# Arduino_DUE_V02b_1.net
KiCad netlist of a schematic drawn in Altium Designer
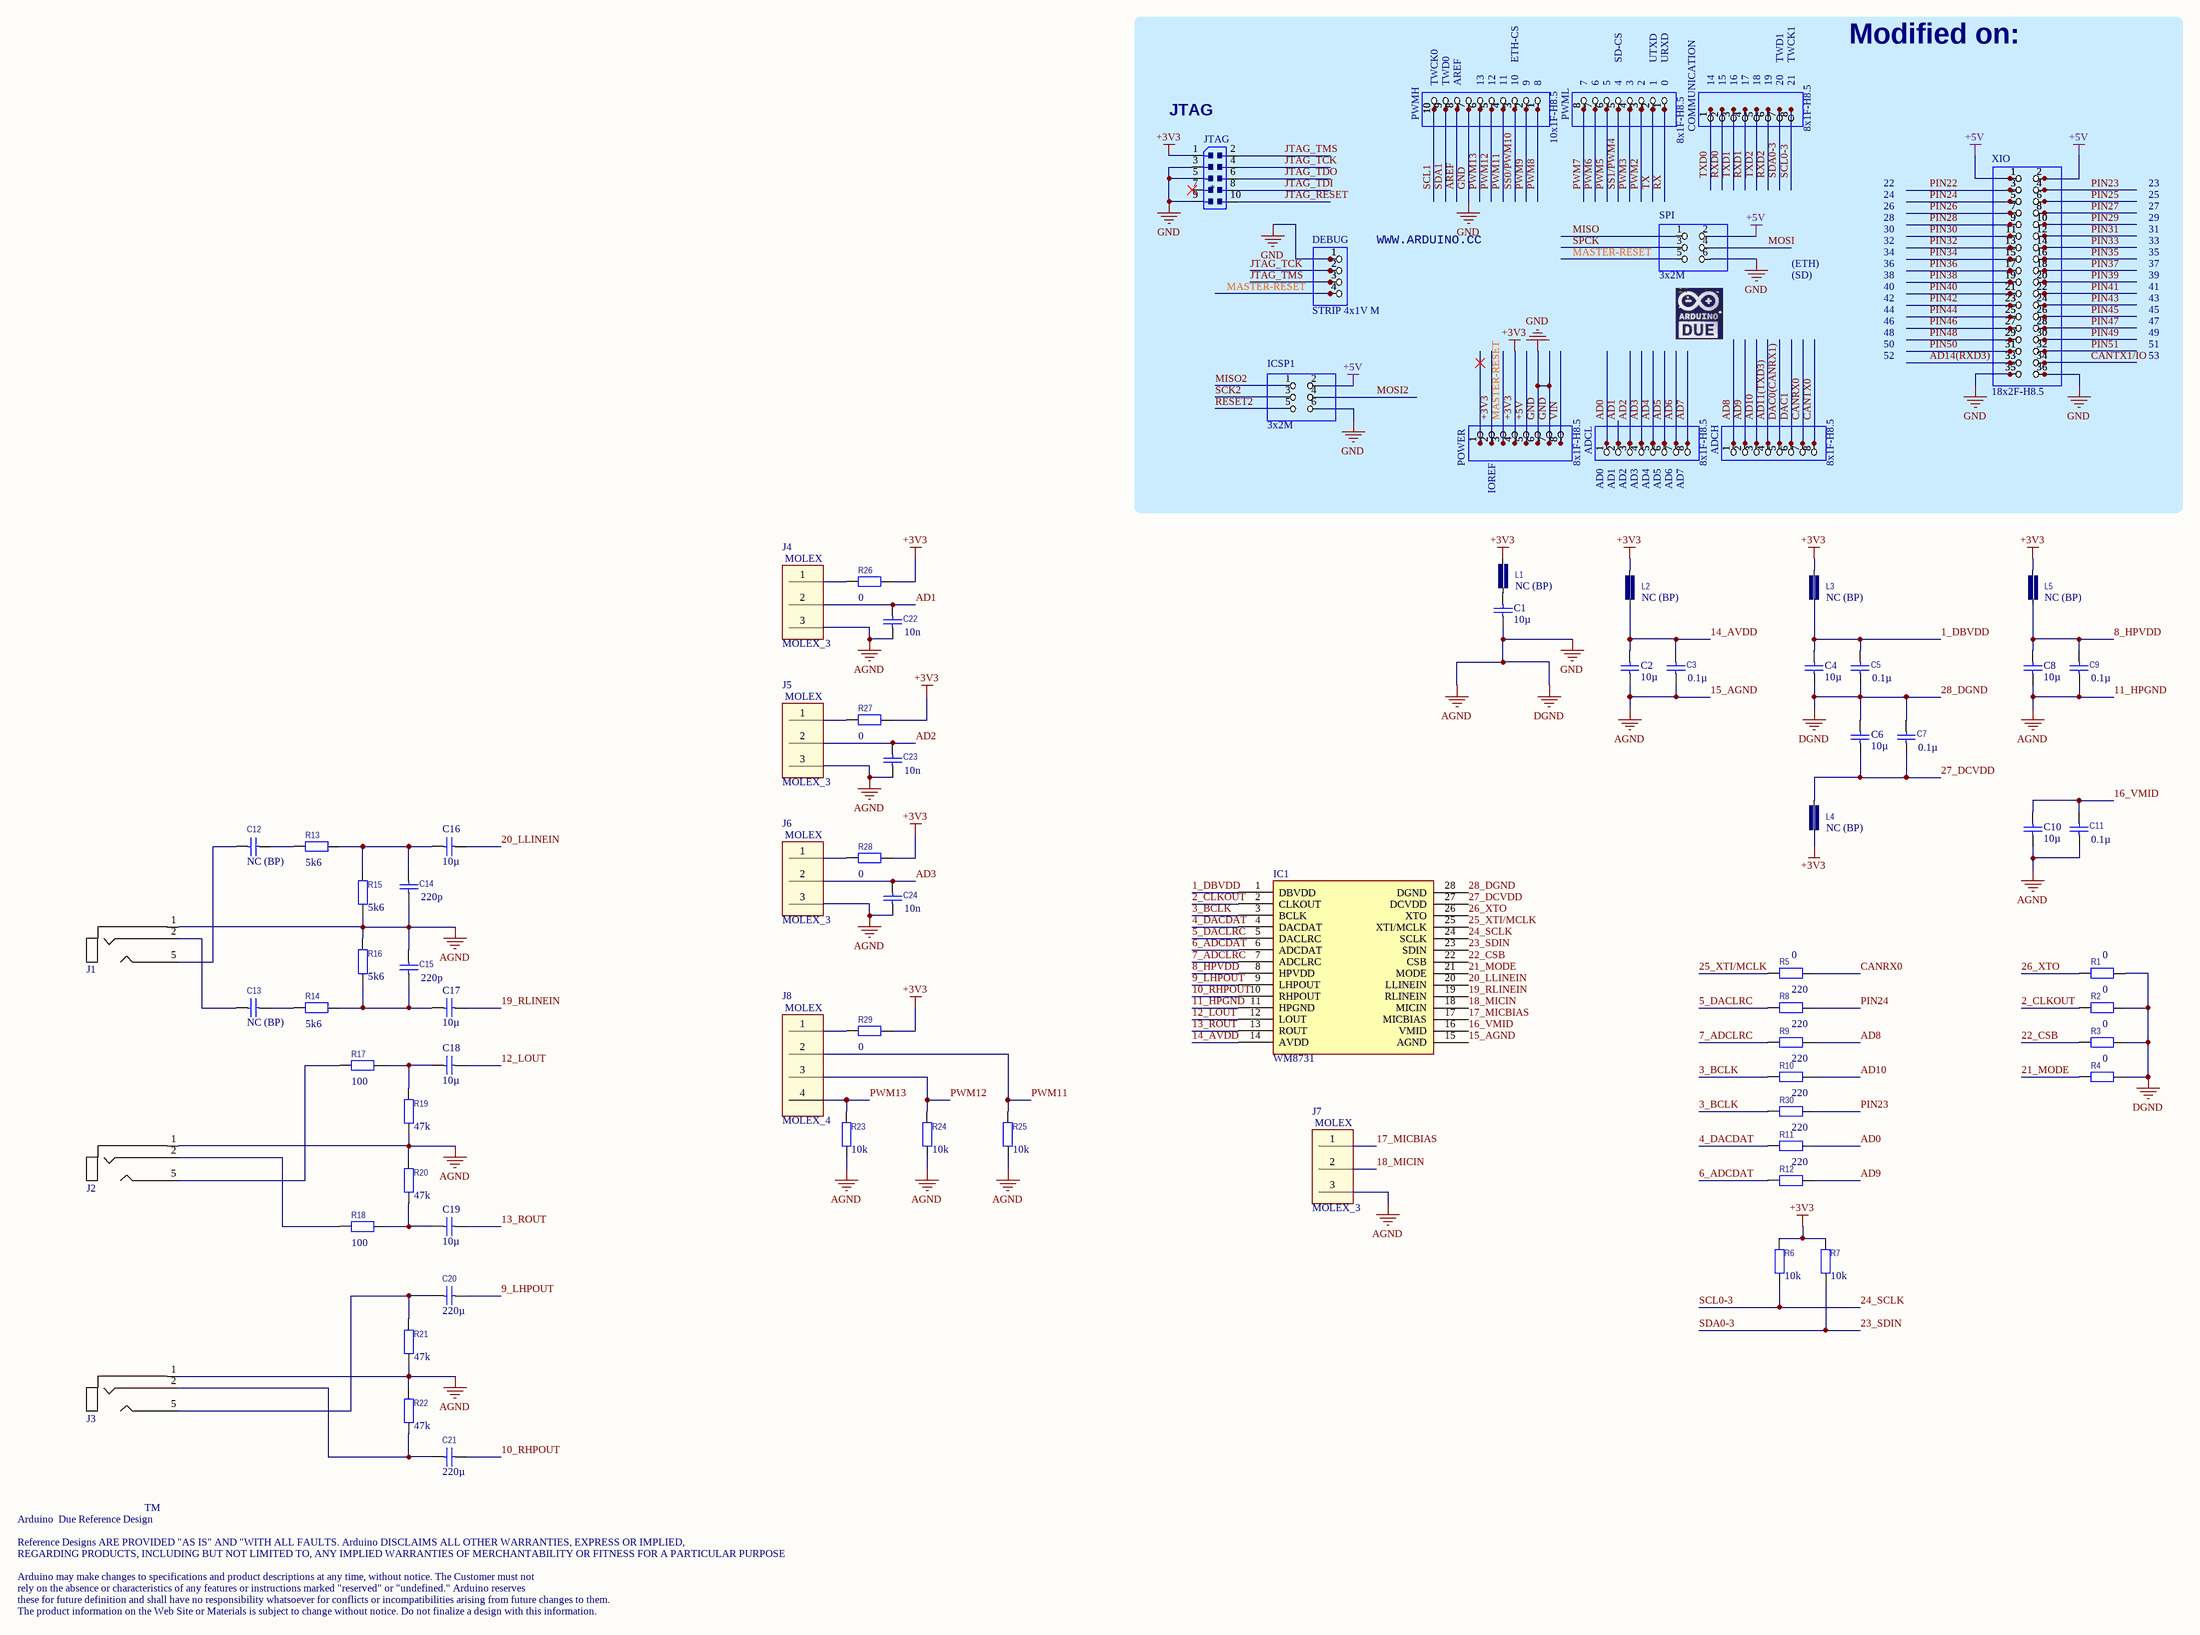
[diagram p0: Arduino_DUE_V02b_1.SchDoc]

(export (version "E")
  (design (tool "Eeschema 10.0.6"))
  (components
    (comp (ref "ADCH") (value "8x1F-H8.5") (footprint "1X08") (libsource (lib "SmartPrj") (part "PINHD-1X8")))
    (comp (ref "ADCL") (value "8x1F-H8.5") (footprint "1X08") (libsource (lib "SmartPrj") (part "PINHD-1X8")))
    (comp (ref "C1")
      (value "10µ")
      (footprint "0603_s")
      (fields (field (name "Comment") "Cap"))
      (libsource (lib "Cap") (part "Cap"))
    )
    (comp (ref "C2")
      (value "10µ")
      (footprint "0603_s")
      (fields (field (name "Comment") "Cap"))
      (libsource (lib "Cap") (part "Cap"))
    )
    (comp (ref "C3")
      (value "0.1µ")
      (footprint "0402_s")
      (fields (field (name "PARTNUMBER") "EA00008430") (field (name "Comment") "Capacitor"))
      (libsource (lib "AVLDiTEST Bauteile") (part "Capacitor"))
    )
    (comp (ref "C4")
      (value "10µ")
      (footprint "0603_s")
      (fields (field (name "Comment") "Cap"))
      (libsource (lib "Cap") (part "Cap"))
    )
    (comp (ref "C5")
      (value "0.1µ")
      (footprint "0402_s")
      (fields (field (name "PARTNUMBER") "EA00008430") (field (name "Comment") "Capacitor"))
      (libsource (lib "AVLDiTEST Bauteile") (part "Capacitor"))
    )
    (comp (ref "C6")
      (value "10µ")
      (footprint "0603_s")
      (fields (field (name "Comment") "Cap"))
      (libsource (lib "Cap") (part "Cap"))
    )
    (comp (ref "C7")
      (value "0.1µ")
      (footprint "0402_s")
      (fields (field (name "PARTNUMBER") "EA00008430") (field (name "Comment") "Capacitor"))
      (libsource (lib "AVLDiTEST Bauteile") (part "Capacitor"))
    )
    (comp (ref "C8")
      (value "10µ")
      (footprint "0603_s")
      (fields (field (name "Comment") "Cap"))
      (libsource (lib "Cap") (part "Cap"))
    )
    (comp (ref "C9")
      (value "0.1µ")
      (footprint "0402_s")
      (fields (field (name "PARTNUMBER") "EA00008430") (field (name "Comment") "Capacitor"))
      (libsource (lib "AVLDiTEST Bauteile") (part "Capacitor"))
    )
    (comp (ref "C10")
      (value "10µ")
      (footprint "0603_s")
      (fields (field (name "Comment") "Cap"))
      (libsource (lib "Cap") (part "Cap"))
    )
    (comp (ref "C11")
      (value "0.1µ")
      (footprint "0402_s")
      (fields (field (name "PARTNUMBER") "EA00008430") (field (name "Comment") "Capacitor"))
      (libsource (lib "AVLDiTEST Bauteile") (part "Capacitor"))
    )
    (comp (ref "C12")
      (value "NC (BP)")
      (footprint "0402_s")
      (fields (field (name "PARTNUMBER") "EA00008430") (field (name "Comment") "Capacitor"))
      (libsource (lib "AVLDiTEST Bauteile") (part "Capacitor"))
    )
    (comp (ref "C13")
      (value "NC (BP)")
      (footprint "0402_s")
      (fields (field (name "PARTNUMBER") "EA00008430") (field (name "Comment") "Capacitor"))
      (libsource (lib "AVLDiTEST Bauteile") (part "Capacitor"))
    )
    (comp (ref "C14")
      (value "220p")
      (footprint "0402_s")
      (fields (field (name "PARTNUMBER") "EA00008430") (field (name "Comment") "Capacitor"))
      (libsource (lib "AVLDiTEST Bauteile") (part "Capacitor"))
    )
    (comp (ref "C15")
      (value "220p")
      (footprint "0402_s")
      (fields (field (name "PARTNUMBER") "EA00008430") (field (name "Comment") "Capacitor"))
      (libsource (lib "AVLDiTEST Bauteile") (part "Capacitor"))
    )
    (comp (ref "C16")
      (value "10µ")
      (footprint "0603_s")
      (fields (field (name "Comment") "Cap"))
      (libsource (lib "Cap") (part "Cap"))
    )
    (comp (ref "C17")
      (value "10µ")
      (footprint "0603_s")
      (fields (field (name "Comment") "Cap"))
      (libsource (lib "Cap") (part "Cap"))
    )
    (comp (ref "C18")
      (value "10µ")
      (footprint "0603_s")
      (fields (field (name "Comment") "Cap"))
      (libsource (lib "Cap") (part "Cap"))
    )
    (comp (ref "C19")
      (value "10µ")
      (footprint "0603_s")
      (fields (field (name "Comment") "Cap"))
      (libsource (lib "Cap") (part "Cap"))
    )
    (comp (ref "C20")
      (value "220µ")
      (footprint "EEEFK0J221P")
      (fields (field (name "PARTNUMBER") "EA00008430") (field (name "Comment") "Capacitor"))
      (libsource (lib "AVLDiTEST Bauteile") (part "Capacitor"))
    )
    (comp (ref "C21")
      (value "220µ")
      (footprint "EEEFK0J221P")
      (fields (field (name "PARTNUMBER") "EA00008430") (field (name "Comment") "Capacitor"))
      (libsource (lib "AVLDiTEST Bauteile") (part "Capacitor"))
    )
    (comp (ref "C22")
      (value "10n")
      (footprint "0402_s")
      (fields (field (name "PARTNUMBER") "EA00008430") (field (name "Comment") "Capacitor"))
      (libsource (lib "AVLDiTEST Bauteile") (part "Capacitor"))
    )
    (comp (ref "C23")
      (value "10n")
      (footprint "0402_s")
      (fields (field (name "PARTNUMBER") "EA00008430") (field (name "Comment") "Capacitor"))
      (libsource (lib "AVLDiTEST Bauteile") (part "Capacitor"))
    )
    (comp (ref "C24")
      (value "10n")
      (footprint "0402_s")
      (fields (field (name "PARTNUMBER") "EA00008430") (field (name "Comment") "Capacitor"))
      (libsource (lib "AVLDiTEST Bauteile") (part "Capacitor"))
    )
    (comp (ref "COMMUNICATION")
      (value "8x1F-H8.5")
      (footprint "1X08")
      (libsource (lib "SmartPrj") (part "PINHD-1X8"))
    )
    (comp (ref "DEBUG")
      (value "STRIP 4x1V M")
      (footprint "1X04")
      (libsource (lib "pinhead") (part "PINHD-1X4"))
    )
    (comp (ref "IC1") (value "WM8731") (footprint "SSOP28") (libsource (lib "CODEC_SHIELD") (part "WM8731")))
    (comp (ref "ICSP1") (value "3x2M") (footprint "2X03") (libsource (lib "SmartPrj") (part "PINHD-2X3")))
    (comp (ref "J1")
      (value "FC68131")
      (footprint "FC68131")
      (libsource (lib "CODEC_SHIELD") (part "FC68131"))
    )
    (comp (ref "J2")
      (value "FC68131")
      (footprint "FC68131")
      (libsource (lib "CODEC_SHIELD") (part "FC68131"))
    )
    (comp (ref "J3")
      (value "FC68131")
      (footprint "FC68131")
      (libsource (lib "CODEC_SHIELD") (part "FC68131"))
    )
    (comp (ref "J4") (value "MOLEX_3") (footprint "254_3") (libsource (lib "CODEC_SHIELD") (part "MOLEX_3")))
    (comp (ref "J5") (value "MOLEX_3") (footprint "254_3") (libsource (lib "CODEC_SHIELD") (part "MOLEX_3")))
    (comp (ref "J6") (value "MOLEX_3") (footprint "254_3") (libsource (lib "CODEC_SHIELD") (part "MOLEX_3")))
    (comp (ref "J7") (value "MOLEX_3") (footprint "254_3") (libsource (lib "CODEC_SHIELD") (part "MOLEX_3")))
    (comp (ref "J8") (value "MOLEX_4") (footprint "254_4") (libsource (lib "CODEC_SHIELD") (part "MOLEX_4")))
    (comp (ref "JTAG")
      (value "*")
      (footprint "PINHEAD_2X05_127")
      (libsource (lib "Arduino_Wifi_shield_v018_tG") (part "PINHEAD_PINHD-2X5PASSO127"))
    )
    (comp (ref "L1")
      (value "NC (BP)")
      (footprint "0402_S")
      (fields (field (name "PARTNUMBER") "EA00008563"))
      (libsource (lib "AVLDiTEST Bauteile") (part "Ferrite_BLM15AG121SN1"))
    )
    (comp (ref "L2")
      (value "NC (BP)")
      (footprint "0402_S")
      (fields (field (name "PARTNUMBER") "EA00008563"))
      (libsource (lib "AVLDiTEST Bauteile") (part "Ferrite_BLM15AG121SN1"))
    )
    (comp (ref "L3")
      (value "NC (BP)")
      (footprint "0402_S")
      (fields (field (name "PARTNUMBER") "EA00008563"))
      (libsource (lib "AVLDiTEST Bauteile") (part "Ferrite_BLM15AG121SN1"))
    )
    (comp (ref "L4")
      (value "NC (BP)")
      (footprint "0402_S")
      (fields (field (name "PARTNUMBER") "EA00008563"))
      (libsource (lib "AVLDiTEST Bauteile") (part "Ferrite_BLM15AG121SN1"))
    )
    (comp (ref "L5")
      (value "NC (BP)")
      (footprint "0402_S")
      (fields (field (name "PARTNUMBER") "EA00008563"))
      (libsource (lib "AVLDiTEST Bauteile") (part "Ferrite_BLM15AG121SN1"))
    )
    (comp (ref "POWER")
      (value "8x1F-H8.5")
      (footprint "1X08")
      (libsource (lib "SmartPrj") (part "PINHD-1X8"))
    )
    (comp (ref "PWMH")
      (value "10x1F-H8.5")
      (footprint "1X10")
      (libsource (lib "SmartPrj") (part "PINHD-1X10"))
    )
    (comp (ref "PWML") (value "8x1F-H8.5") (footprint "1X08") (libsource (lib "SmartPrj") (part "PINHD-1X8")))
    (comp (ref "R1")
      (value "0")
      (footprint "0402_s")
      (fields (field (name "PARTNUMBER") "EA00008473"))
      (libsource (lib "") (part "Resistor_2"))
    )
    (comp (ref "R2")
      (value "0")
      (footprint "0402_s")
      (fields (field (name "PARTNUMBER") "EA00008473"))
      (libsource (lib "") (part "Resistor_2"))
    )
    (comp (ref "R3")
      (value "0")
      (footprint "0402_s")
      (fields (field (name "PARTNUMBER") "EA00008473"))
      (libsource (lib "") (part "Resistor_2"))
    )
    (comp (ref "R4")
      (value "0")
      (footprint "0402_s")
      (fields (field (name "PARTNUMBER") "EA00008473"))
      (libsource (lib "") (part "Resistor_2"))
    )
    (comp (ref "R5")
      (value "0")
      (footprint "0402_s")
      (fields (field (name "PARTNUMBER") "EA00008473"))
      (libsource (lib "") (part "Resistor_2"))
    )
    (comp (ref "R6")
      (value "10k")
      (footprint "0402_s")
      (fields (field (name "PARTNUMBER") "EA00008473"))
      (libsource (lib "AVLDiTEST Bauteile") (part "Resistor"))
    )
    (comp (ref "R7")
      (value "10k")
      (footprint "0402_s")
      (fields (field (name "PARTNUMBER") "EA00008473"))
      (libsource (lib "AVLDiTEST Bauteile") (part "Resistor"))
    )
    (comp (ref "R8")
      (value "220")
      (footprint "0402_s")
      (fields (field (name "PARTNUMBER") "EA00008473"))
      (libsource (lib "") (part "Resistor_2"))
    )
    (comp (ref "R9")
      (value "220")
      (footprint "0402_s")
      (fields (field (name "PARTNUMBER") "EA00008473"))
      (libsource (lib "") (part "Resistor_2"))
    )
    (comp (ref "R10")
      (value "220")
      (footprint "0402_s")
      (fields (field (name "PARTNUMBER") "EA00008473"))
      (libsource (lib "") (part "Resistor_2"))
    )
    (comp (ref "R11")
      (value "220")
      (footprint "0402_s")
      (fields (field (name "PARTNUMBER") "EA00008473"))
      (libsource (lib "") (part "Resistor_2"))
    )
    (comp (ref "R12")
      (value "220")
      (footprint "0402_s")
      (fields (field (name "PARTNUMBER") "EA00008473"))
      (libsource (lib "") (part "Resistor_2"))
    )
    (comp (ref "R13")
      (value "5k6")
      (footprint "0402_s")
      (fields (field (name "PARTNUMBER") "EA00008473"))
      (libsource (lib "") (part "Resistor_1"))
    )
    (comp (ref "R14")
      (value "5k6")
      (footprint "0402_s")
      (fields (field (name "PARTNUMBER") "EA00008473"))
      (libsource (lib "") (part "Resistor_1"))
    )
    (comp (ref "R15")
      (value "5k6")
      (footprint "0402_s")
      (fields (field (name "PARTNUMBER") "EA00008473"))
      (libsource (lib "AVLDiTEST Bauteile") (part "Resistor"))
    )
    (comp (ref "R16")
      (value "5k6")
      (footprint "0402_s")
      (fields (field (name "PARTNUMBER") "EA00008473"))
      (libsource (lib "AVLDiTEST Bauteile") (part "Resistor"))
    )
    (comp (ref "R17")
      (value "100")
      (footprint "0402_s")
      (fields (field (name "PARTNUMBER") "EA00008473"))
      (libsource (lib "") (part "Resistor_1"))
    )
    (comp (ref "R18")
      (value "100")
      (footprint "0402_s")
      (fields (field (name "PARTNUMBER") "EA00008473"))
      (libsource (lib "") (part "Resistor_1"))
    )
    (comp (ref "R19")
      (value "47k")
      (footprint "0402_s")
      (fields (field (name "PARTNUMBER") "EA00008473"))
      (libsource (lib "AVLDiTEST Bauteile") (part "Resistor"))
    )
    (comp (ref "R20")
      (value "47k")
      (footprint "0402_s")
      (fields (field (name "PARTNUMBER") "EA00008473"))
      (libsource (lib "AVLDiTEST Bauteile") (part "Resistor"))
    )
    (comp (ref "R21")
      (value "47k")
      (footprint "0402_s")
      (fields (field (name "PARTNUMBER") "EA00008473"))
      (libsource (lib "AVLDiTEST Bauteile") (part "Resistor"))
    )
    (comp (ref "R22")
      (value "47k")
      (footprint "0402_s")
      (fields (field (name "PARTNUMBER") "EA00008473"))
      (libsource (lib "AVLDiTEST Bauteile") (part "Resistor"))
    )
    (comp (ref "R23")
      (value "10k")
      (footprint "0402_s")
      (fields (field (name "PARTNUMBER") "EA00008473"))
      (libsource (lib "AVLDiTEST Bauteile") (part "Resistor"))
    )
    (comp (ref "R24")
      (value "10k")
      (footprint "0402_s")
      (fields (field (name "PARTNUMBER") "EA00008473"))
      (libsource (lib "AVLDiTEST Bauteile") (part "Resistor"))
    )
    (comp (ref "R25")
      (value "10k")
      (footprint "0402_s")
      (fields (field (name "PARTNUMBER") "EA00008473"))
      (libsource (lib "AVLDiTEST Bauteile") (part "Resistor"))
    )
    (comp (ref "R26")
      (value "0")
      (footprint "0402_s")
      (fields (field (name "PARTNUMBER") "EA00008473"))
      (libsource (lib "") (part "Resistor_1"))
    )
    (comp (ref "R27")
      (value "0")
      (footprint "0402_s")
      (fields (field (name "PARTNUMBER") "EA00008473"))
      (libsource (lib "") (part "Resistor_1"))
    )
    (comp (ref "R28")
      (value "0")
      (footprint "0402_s")
      (fields (field (name "PARTNUMBER") "EA00008473"))
      (libsource (lib "") (part "Resistor_1"))
    )
    (comp (ref "R29")
      (value "0")
      (footprint "0402_s")
      (fields (field (name "PARTNUMBER") "EA00008473"))
      (libsource (lib "") (part "Resistor_1"))
    )
    (comp (ref "R30")
      (value "220")
      (footprint "0402_s")
      (fields (field (name "PARTNUMBER") "EA00008473"))
      (libsource (lib "") (part "Resistor_2"))
    )
    (comp (ref "SPI") (value "3x2M") (footprint "2X03") (libsource (lib "SmartPrj") (part "PINHD-2X3")))
    (comp (ref "XIO")
      (value "18x2F-H8.5")
      (footprint "2X18")
      (libsource (lib "SmartPrj") (part "PINHD-2X18"))
    )
  )
  (nets
    (net (code "1") (name "+3V3") (class "Default")
      (node (ref "JTAG") (pin "1") (pinfunction "1_1") (pintype "passive"))
      (node (ref "L1") (pin "2") (pinfunction "2_2") (pintype "passive"))
      (node (ref "L2") (pin "2") (pinfunction "2_2") (pintype "passive"))
      (node (ref "L3") (pin "2") (pinfunction "2_2") (pintype "passive"))
      (node (ref "L4") (pin "1") (pinfunction "1_1") (pintype "passive"))
      (node (ref "L5") (pin "2") (pinfunction "2_2") (pintype "passive"))
      (node (ref "POWER") (pin "2") (pinfunction "2_2") (pintype "passive"))
      (node (ref "POWER") (pin "4") (pinfunction "4_4") (pintype "passive"))
      (node (ref "R26") (pin "1") (pinfunction "1_1") (pintype "passive"))
      (node (ref "R27") (pin "1") (pinfunction "1_1") (pintype "passive"))
      (node (ref "R28") (pin "1") (pinfunction "1_1") (pintype "passive"))
      (node (ref "R29") (pin "1") (pinfunction "1_1") (pintype "passive"))
      (node (ref "R6") (pin "2") (pinfunction "2_2") (pintype "passive"))
      (node (ref "R7") (pin "2") (pinfunction "2_2") (pintype "passive"))
    )
    (net (code "2") (name "+5V") (class "Default")
      (node (ref "ICSP1") (pin "2") (pinfunction "2_2") (pintype "passive"))
      (node (ref "POWER") (pin "5") (pinfunction "5_5") (pintype "passive"))
      (node (ref "SPI") (pin "2") (pinfunction "2_2") (pintype "passive"))
      (node (ref "XIO") (pin "1") (pinfunction "1_1") (pintype "passive"))
      (node (ref "XIO") (pin "2") (pinfunction "2_2") (pintype "passive"))
    )
    (net (code "3") (name "/1_DBVDD") (class "Default")
      (node (ref "C4") (pin "2") (pinfunction "2_2") (pintype "passive"))
      (node (ref "C5") (pin "2") (pinfunction "2_2") (pintype "passive"))
      (node (ref "IC1") (pin "1") (pinfunction "DBVDD_1") (pintype "passive"))
      (node (ref "L3") (pin "1") (pinfunction "1_1") (pintype "passive"))
    )
    (net (code "4") (name "/2_CLKOUT") (class "Default")
      (node (ref "IC1") (pin "2") (pinfunction "CLKOUT_2") (pintype "passive"))
      (node (ref "R2") (pin "1") (pinfunction "1_1") (pintype "passive"))
    )
    (net (code "5") (name "/3_BCLK") (class "Default")
      (node (ref "IC1") (pin "3") (pinfunction "BCLK_3") (pintype "passive"))
      (node (ref "R10") (pin "1") (pinfunction "1_1") (pintype "passive"))
      (node (ref "R30") (pin "1") (pinfunction "1_1") (pintype "passive"))
    )
    (net (code "6") (name "/4_DACDAT") (class "Default")
      (node (ref "IC1") (pin "4") (pinfunction "DACDAT_4") (pintype "passive"))
      (node (ref "R11") (pin "1") (pinfunction "1_1") (pintype "passive"))
    )
    (net (code "7") (name "/5_DACLRC") (class "Default")
      (node (ref "IC1") (pin "5") (pinfunction "DACLRC_5") (pintype "passive"))
      (node (ref "R8") (pin "1") (pinfunction "1_1") (pintype "passive"))
    )
    (net (code "8") (name "/6_ADCDAT") (class "Default")
      (node (ref "IC1") (pin "6") (pinfunction "ADCDAT_6") (pintype "passive"))
      (node (ref "R12") (pin "1") (pinfunction "1_1") (pintype "passive"))
    )
    (net (code "9") (name "/7_ADCLRC") (class "Default")
      (node (ref "IC1") (pin "7") (pinfunction "ADCLRC_7") (pintype "passive"))
      (node (ref "R9") (pin "1") (pinfunction "1_1") (pintype "passive"))
    )
    (net (code "10") (name "/8_HPVDD") (class "Default")
      (node (ref "C8") (pin "2") (pinfunction "2_2") (pintype "passive"))
      (node (ref "C9") (pin "2") (pinfunction "2_2") (pintype "passive"))
      (node (ref "IC1") (pin "8") (pinfunction "HPVDD_8") (pintype "passive"))
      (node (ref "L5") (pin "1") (pinfunction "1_1") (pintype "passive"))
    )
    (net (code "11") (name "/9_LHPOUT") (class "Default")
      (node (ref "C20") (pin "1") (pinfunction "1_1") (pintype "passive"))
      (node (ref "IC1") (pin "9") (pinfunction "LHPOUT_9") (pintype "passive"))
    )
    (net (code "12") (name "/10_RHPOUT") (class "Default")
      (node (ref "C21") (pin "1") (pinfunction "1_1") (pintype "passive"))
      (node (ref "IC1") (pin "10") (pinfunction "RHPOUT_10") (pintype "passive"))
    )
    (net (code "13") (name "/12_LOUT") (class "Default")
      (node (ref "C18") (pin "1") (pinfunction "1_1") (pintype "passive"))
      (node (ref "IC1") (pin "12") (pinfunction "LOUT_12") (pintype "passive"))
    )
    (net (code "14") (name "/13_ROUT") (class "Default")
      (node (ref "C19") (pin "1") (pinfunction "1_1") (pintype "passive"))
      (node (ref "IC1") (pin "13") (pinfunction "ROUT_13") (pintype "passive"))
    )
    (net (code "15") (name "/14_AVDD") (class "Default")
      (node (ref "C2") (pin "2") (pinfunction "2_2") (pintype "passive"))
      (node (ref "C3") (pin "2") (pinfunction "2_2") (pintype "passive"))
      (node (ref "IC1") (pin "14") (pinfunction "AVDD_14") (pintype "passive"))
      (node (ref "L2") (pin "1") (pinfunction "1_1") (pintype "passive"))
    )
    (net (code "16") (name "/16_VMID") (class "Default")
      (node (ref "C10") (pin "2") (pinfunction "2_2") (pintype "passive"))
      (node (ref "C11") (pin "2") (pinfunction "2_2") (pintype "passive"))
      (node (ref "IC1") (pin "16") (pinfunction "VMID_16") (pintype "passive"))
    )
    (net (code "17") (name "/17_MICBIAS") (class "Default")
      (node (ref "IC1") (pin "17") (pinfunction "MICBIAS_17") (pintype "passive"))
      (node (ref "J7") (pin "1") (pinfunction "1_1") (pintype "passive"))
    )
    (net (code "18") (name "/18_MICIN") (class "Default")
      (node (ref "IC1") (pin "18") (pinfunction "MICIN_18") (pintype "passive"))
      (node (ref "J7") (pin "2") (pinfunction "2_2") (pintype "passive"))
    )
    (net (code "19") (name "/19_RLINEIN") (class "Default")
      (node (ref "C17") (pin "1") (pinfunction "1_1") (pintype "passive"))
      (node (ref "IC1") (pin "19") (pinfunction "RLINEIN_19") (pintype "passive"))
    )
    (net (code "20") (name "/20_LLINEIN") (class "Default")
      (node (ref "C16") (pin "1") (pinfunction "1_1") (pintype "passive"))
      (node (ref "IC1") (pin "20") (pinfunction "LLINEIN_20") (pintype "passive"))
    )
    (net (code "21") (name "/21_MODE") (class "Default")
      (node (ref "IC1") (pin "21") (pinfunction "MODE_21") (pintype "passive"))
      (node (ref "R4") (pin "1") (pinfunction "1_1") (pintype "passive"))
    )
    (net (code "22") (name "/22_CSB") (class "Default")
      (node (ref "IC1") (pin "22") (pinfunction "CSB_22") (pintype "passive"))
      (node (ref "R3") (pin "1") (pinfunction "1_1") (pintype "passive"))
    )
    (net (code "23") (name "/23_SDIN") (class "Default")
      (node (ref "COMMUNICATION") (pin "7") (pinfunction "7_7") (pintype "passive"))
      (node (ref "IC1") (pin "23") (pinfunction "SDIN_23") (pintype "passive"))
      (node (ref "R7") (pin "1") (pinfunction "1_1") (pintype "passive"))
    )
    (net (code "24") (name "/24_SCLK") (class "Default")
      (node (ref "COMMUNICATION") (pin "8") (pinfunction "8_8") (pintype "passive"))
      (node (ref "IC1") (pin "24") (pinfunction "SCLK_24") (pintype "passive"))
      (node (ref "R6") (pin "1") (pinfunction "1_1") (pintype "passive"))
    )
    (net (code "25") (name "/25_XTI{slash}MCLK") (class "Default")
      (node (ref "IC1") (pin "25") (pinfunction "XTI/MCLK_25") (pintype "passive"))
      (node (ref "R5") (pin "1") (pinfunction "1_1") (pintype "passive"))
    )
    (net (code "26") (name "/26_XTO") (class "Default")
      (node (ref "IC1") (pin "26") (pinfunction "XTO_26") (pintype "passive"))
      (node (ref "R1") (pin "1") (pinfunction "1_1") (pintype "passive"))
    )
    (net (code "27") (name "/27_DCVDD") (class "Default")
      (node (ref "C6") (pin "1") (pinfunction "1_1") (pintype "passive"))
      (node (ref "C7") (pin "1") (pinfunction "1_1") (pintype "passive"))
      (node (ref "IC1") (pin "27") (pinfunction "DCVDD_27") (pintype "passive"))
      (node (ref "L4") (pin "2") (pinfunction "2_2") (pintype "passive"))
    )
    (net (code "28") (name "/AD0") (class "Default")
      (node (ref "ADCL") (pin "1") (pinfunction "1_1") (pintype "passive"))
      (node (ref "R11") (pin "2") (pinfunction "2_2") (pintype "passive"))
    )
    (net (code "29") (name "/AD1") (class "Default")
      (node (ref "ADCL") (pin "2") (pinfunction "2_2") (pintype "passive"))
      (node (ref "C22") (pin "2") (pinfunction "2_2") (pintype "passive"))
      (node (ref "J4") (pin "2") (pinfunction "2_2") (pintype "passive"))
    )
    (net (code "30") (name "/AD2") (class "Default")
      (node (ref "ADCL") (pin "3") (pinfunction "3_3") (pintype "passive"))
      (node (ref "C23") (pin "2") (pinfunction "2_2") (pintype "passive"))
      (node (ref "J5") (pin "2") (pinfunction "2_2") (pintype "passive"))
    )
    (net (code "31") (name "/AD3") (class "Default")
      (node (ref "ADCL") (pin "4") (pinfunction "4_4") (pintype "passive"))
      (node (ref "C24") (pin "2") (pinfunction "2_2") (pintype "passive"))
      (node (ref "J6") (pin "2") (pinfunction "2_2") (pintype "passive"))
    )
    (net (code "32") (name "/AD4") (class "Default")
      (node (ref "ADCL") (pin "5") (pinfunction "5_5") (pintype "passive"))
    )
    (net (code "33") (name "/AD5") (class "Default")
      (node (ref "ADCL") (pin "6") (pinfunction "6_6") (pintype "passive"))
    )
    (net (code "34") (name "/AD6") (class "Default")
      (node (ref "ADCL") (pin "7") (pinfunction "7_7") (pintype "passive"))
    )
    (net (code "35") (name "/AD7") (class "Default")
      (node (ref "ADCL") (pin "8") (pinfunction "8_8") (pintype "passive"))
    )
    (net (code "36") (name "/AD8") (class "Default")
      (node (ref "ADCH") (pin "1") (pinfunction "1_1") (pintype "passive"))
      (node (ref "R9") (pin "2") (pinfunction "2_2") (pintype "passive"))
    )
    (net (code "37") (name "/AD9") (class "Default")
      (node (ref "ADCH") (pin "2") (pinfunction "2_2") (pintype "passive"))
      (node (ref "R12") (pin "2") (pinfunction "2_2") (pintype "passive"))
    )
    (net (code "38") (name "/AD10") (class "Default")
      (node (ref "ADCH") (pin "3") (pinfunction "3_3") (pintype "passive"))
      (node (ref "R10") (pin "2") (pinfunction "2_2") (pintype "passive"))
    )
    (net (code "39") (name "/AD11(TXD3)") (class "Default")
      (node (ref "ADCH") (pin "4") (pinfunction "4_4") (pintype "passive"))
    )
    (net (code "40") (name "/AD14(RXD3)") (class "Default")
      (node (ref "XIO") (pin "33") (pinfunction "33_33") (pintype "passive"))
    )
    (net (code "41") (name "/AREF") (class "Default")
      (node (ref "PWMH") (pin "8") (pinfunction "8_8") (pintype "passive"))
    )
    (net (code "42") (name "/CANRX0") (class "Default")
      (node (ref "ADCH") (pin "7") (pinfunction "7_7") (pintype "passive"))
      (node (ref "R5") (pin "2") (pinfunction "2_2") (pintype "passive"))
    )
    (net (code "43") (name "/CANTX0") (class "Default")
      (node (ref "ADCH") (pin "8") (pinfunction "8_8") (pintype "passive"))
    )
    (net (code "44") (name "/CANTX1{slash}IO") (class "Default")
      (node (ref "XIO") (pin "34") (pinfunction "34_34") (pintype "passive"))
    )
    (net (code "45") (name "/DAC0(CANRX1)") (class "Default")
      (node (ref "ADCH") (pin "5") (pinfunction "5_5") (pintype "passive"))
    )
    (net (code "46") (name "/DAC1") (class "Default")
      (node (ref "ADCH") (pin "6") (pinfunction "6_6") (pintype "passive"))
    )
    (net (code "47") (name "/JTAG_RESET") (class "Default")
      (node (ref "JTAG") (pin "10") (pinfunction "10_10") (pintype "passive"))
    )
    (net (code "48") (name "/JTAG_TCK") (class "Default")
      (node (ref "DEBUG") (pin "2") (pinfunction "2_2") (pintype "passive"))
      (node (ref "JTAG") (pin "4") (pinfunction "4_4") (pintype "passive"))
    )
    (net (code "49") (name "/JTAG_TDI") (class "Default")
      (node (ref "JTAG") (pin "8") (pinfunction "8_8") (pintype "passive"))
    )
    (net (code "50") (name "/JTAG_TDO") (class "Default")
      (node (ref "JTAG") (pin "6") (pinfunction "6_6") (pintype "passive"))
    )
    (net (code "51") (name "/JTAG_TMS") (class "Default")
      (node (ref "DEBUG") (pin "3") (pinfunction "3_3") (pintype "passive"))
      (node (ref "JTAG") (pin "2") (pinfunction "2_2") (pintype "passive"))
    )
    (net (code "52") (name "/MASTER-RESET") (class "Default")
      (node (ref "DEBUG") (pin "4") (pinfunction "4_4") (pintype "passive"))
      (node (ref "POWER") (pin "3") (pinfunction "3_3") (pintype "passive"))
      (node (ref "SPI") (pin "5") (pinfunction "5_5") (pintype "passive"))
    )
    (net (code "53") (name "/MISO") (class "Default")
      (node (ref "SPI") (pin "1") (pinfunction "1_1") (pintype "passive"))
    )
    (net (code "54") (name "/MISO2") (class "Default")
      (node (ref "ICSP1") (pin "1") (pinfunction "1_1") (pintype "passive"))
    )
    (net (code "55") (name "/MOSI") (class "Default")
      (node (ref "SPI") (pin "4") (pinfunction "4_4") (pintype "passive"))
    )
    (net (code "56") (name "/MOSI2") (class "Default")
      (node (ref "ICSP1") (pin "4") (pinfunction "4_4") (pintype "passive"))
    )
    (net (code "57") (name "/PIN22") (class "Default")
      (node (ref "XIO") (pin "3") (pinfunction "3_3") (pintype "passive"))
    )
    (net (code "58") (name "/PIN23") (class "Default")
      (node (ref "R30") (pin "2") (pinfunction "2_2") (pintype "passive"))
      (node (ref "XIO") (pin "4") (pinfunction "4_4") (pintype "passive"))
    )
    (net (code "59") (name "/PIN24") (class "Default")
      (node (ref "R8") (pin "2") (pinfunction "2_2") (pintype "passive"))
      (node (ref "XIO") (pin "5") (pinfunction "5_5") (pintype "passive"))
    )
    (net (code "60") (name "/PIN25") (class "Default")
      (node (ref "XIO") (pin "6") (pinfunction "6_6") (pintype "passive"))
    )
    (net (code "61") (name "/PIN26") (class "Default")
      (node (ref "XIO") (pin "7") (pinfunction "7_7") (pintype "passive"))
    )
    (net (code "62") (name "/PIN27") (class "Default")
      (node (ref "XIO") (pin "8") (pinfunction "8_8") (pintype "passive"))
    )
    (net (code "63") (name "/PIN28") (class "Default")
      (node (ref "XIO") (pin "9") (pinfunction "9_9") (pintype "passive"))
    )
    (net (code "64") (name "/PIN29") (class "Default")
      (node (ref "XIO") (pin "10") (pinfunction "10_10") (pintype "passive"))
    )
    (net (code "65") (name "/PIN30") (class "Default")
      (node (ref "XIO") (pin "11") (pinfunction "11_11") (pintype "passive"))
    )
    (net (code "66") (name "/PIN31") (class "Default")
      (node (ref "XIO") (pin "12") (pinfunction "12_12") (pintype "passive"))
    )
    (net (code "67") (name "/PIN32") (class "Default")
      (node (ref "XIO") (pin "13") (pinfunction "13_13") (pintype "passive"))
    )
    (net (code "68") (name "/PIN33") (class "Default")
      (node (ref "XIO") (pin "14") (pinfunction "14_14") (pintype "passive"))
    )
    (net (code "69") (name "/PIN34") (class "Default")
      (node (ref "XIO") (pin "15") (pinfunction "15_15") (pintype "passive"))
    )
    (net (code "70") (name "/PIN35") (class "Default")
      (node (ref "XIO") (pin "16") (pinfunction "16_16") (pintype "passive"))
    )
    (net (code "71") (name "/PIN36") (class "Default")
      (node (ref "XIO") (pin "17") (pinfunction "17_17") (pintype "passive"))
    )
    (net (code "72") (name "/PIN37") (class "Default")
      (node (ref "XIO") (pin "18") (pinfunction "18_18") (pintype "passive"))
    )
    (net (code "73") (name "/PIN38") (class "Default")
      (node (ref "XIO") (pin "19") (pinfunction "19_19") (pintype "passive"))
    )
    (net (code "74") (name "/PIN39") (class "Default")
      (node (ref "XIO") (pin "20") (pinfunction "20_20") (pintype "passive"))
    )
    (net (code "75") (name "/PIN40") (class "Default")
      (node (ref "XIO") (pin "21") (pinfunction "21_21") (pintype "passive"))
    )
    (net (code "76") (name "/PIN41") (class "Default")
      (node (ref "XIO") (pin "22") (pinfunction "22_22") (pintype "passive"))
    )
    (net (code "77") (name "/PIN42") (class "Default")
      (node (ref "XIO") (pin "23") (pinfunction "23_23") (pintype "passive"))
    )
    (net (code "78") (name "/PIN43") (class "Default")
      (node (ref "XIO") (pin "24") (pinfunction "24_24") (pintype "passive"))
    )
    (net (code "79") (name "/PIN44") (class "Default")
      (node (ref "XIO") (pin "25") (pinfunction "25_25") (pintype "passive"))
    )
    (net (code "80") (name "/PIN45") (class "Default")
      (node (ref "XIO") (pin "26") (pinfunction "26_26") (pintype "passive"))
    )
    (net (code "81") (name "/PIN46") (class "Default")
      (node (ref "XIO") (pin "27") (pinfunction "27_27") (pintype "passive"))
    )
    (net (code "82") (name "/PIN47") (class "Default")
      (node (ref "XIO") (pin "28") (pinfunction "28_28") (pintype "passive"))
    )
    (net (code "83") (name "/PIN48") (class "Default")
      (node (ref "XIO") (pin "29") (pinfunction "29_29") (pintype "passive"))
    )
    (net (code "84") (name "/PIN49") (class "Default")
      (node (ref "XIO") (pin "30") (pinfunction "30_30") (pintype "passive"))
    )
    (net (code "85") (name "/PIN50") (class "Default")
      (node (ref "XIO") (pin "31") (pinfunction "31_31") (pintype "passive"))
    )
    (net (code "86") (name "/PIN51") (class "Default")
      (node (ref "XIO") (pin "32") (pinfunction "32_32") (pintype "passive"))
    )
    (net (code "87") (name "/PWM2") (class "Default")
      (node (ref "PWML") (pin "3") (pinfunction "3_3") (pintype "passive"))
    )
    (net (code "88") (name "/PWM3") (class "Default")
      (node (ref "PWML") (pin "4") (pinfunction "4_4") (pintype "passive"))
    )
    (net (code "89") (name "/PWM5") (class "Default")
      (node (ref "PWML") (pin "6") (pinfunction "6_6") (pintype "passive"))
    )
    (net (code "90") (name "/PWM6") (class "Default")
      (node (ref "PWML") (pin "7") (pinfunction "7_7") (pintype "passive"))
    )
    (net (code "91") (name "/PWM7") (class "Default")
      (node (ref "PWML") (pin "8") (pinfunction "8_8") (pintype "passive"))
    )
    (net (code "92") (name "/PWM8") (class "Default")
      (node (ref "PWMH") (pin "1") (pinfunction "1_1") (pintype "passive"))
    )
    (net (code "93") (name "/PWM9") (class "Default")
      (node (ref "PWMH") (pin "2") (pinfunction "2_2") (pintype "passive"))
    )
    (net (code "94") (name "/PWM11") (class "Default")
      (node (ref "J8") (pin "2") (pinfunction "2_2") (pintype "passive"))
      (node (ref "PWMH") (pin "4") (pinfunction "4_4") (pintype "passive"))
      (node (ref "R25") (pin "2") (pinfunction "2_2") (pintype "passive"))
    )
    (net (code "95") (name "/PWM12") (class "Default")
      (node (ref "J8") (pin "3") (pinfunction "3_3") (pintype "passive"))
      (node (ref "PWMH") (pin "5") (pinfunction "5_5") (pintype "passive"))
      (node (ref "R24") (pin "2") (pinfunction "2_2") (pintype "passive"))
    )
    (net (code "96") (name "/PWM13") (class "Default")
      (node (ref "J8") (pin "4") (pinfunction "4_4") (pintype "passive"))
      (node (ref "PWMH") (pin "6") (pinfunction "6_6") (pintype "passive"))
      (node (ref "R23") (pin "2") (pinfunction "2_2") (pintype "passive"))
    )
    (net (code "97") (name "/RESET2") (class "Default")
      (node (ref "ICSP1") (pin "5") (pinfunction "5_5") (pintype "passive"))
    )
    (net (code "98") (name "/RX") (class "Default")
      (node (ref "PWML") (pin "1") (pinfunction "1_1") (pintype "passive"))
    )
    (net (code "99") (name "/RXD0") (class "Default")
      (node (ref "COMMUNICATION") (pin "2") (pinfunction "2_2") (pintype "passive"))
    )
    (net (code "100") (name "/RXD1") (class "Default")
      (node (ref "COMMUNICATION") (pin "4") (pinfunction "4_4") (pintype "passive"))
    )
    (net (code "101") (name "/RXD2") (class "Default")
      (node (ref "COMMUNICATION") (pin "6") (pinfunction "6_6") (pintype "passive"))
    )
    (net (code "102") (name "/SCK2") (class "Default")
      (node (ref "ICSP1") (pin "3") (pinfunction "3_3") (pintype "passive"))
    )
    (net (code "103") (name "/SCL1") (class "Default")
      (node (ref "PWMH") (pin "10") (pinfunction "10_10") (pintype "passive"))
    )
    (net (code "104") (name "/SDA1") (class "Default")
      (node (ref "PWMH") (pin "9") (pinfunction "9_9") (pintype "passive"))
    )
    (net (code "105") (name "/SPCK") (class "Default")
      (node (ref "SPI") (pin "3") (pinfunction "3_3") (pintype "passive"))
    )
    (net (code "106") (name "/SS0{slash}PWM10") (class "Default")
      (node (ref "PWMH") (pin "3") (pinfunction "3_3") (pintype "passive"))
    )
    (net (code "107") (name "/SS1{slash}PWM4") (class "Default")
      (node (ref "PWML") (pin "5") (pinfunction "5_5") (pintype "passive"))
    )
    (net (code "108") (name "/TX") (class "Default")
      (node (ref "PWML") (pin "2") (pinfunction "2_2") (pintype "passive"))
    )
    (net (code "109") (name "/TXD0") (class "Default")
      (node (ref "COMMUNICATION") (pin "1") (pinfunction "1_1") (pintype "passive"))
    )
    (net (code "110") (name "/TXD1") (class "Default")
      (node (ref "COMMUNICATION") (pin "3") (pinfunction "3_3") (pintype "passive"))
    )
    (net (code "111") (name "/TXD2") (class "Default")
      (node (ref "COMMUNICATION") (pin "5") (pinfunction "5_5") (pintype "passive"))
    )
    (net (code "112") (name "/VIN") (class "Default")
      (node (ref "POWER") (pin "8") (pinfunction "8_8") (pintype "passive"))
    )
    (net (code "113") (name "AGND") (class "Default")
      (node (ref "C1") (pin "1") (pinfunction "1_1") (pintype "passive"))
      (node (ref "C10") (pin "1") (pinfunction "1_1") (pintype "passive"))
      (node (ref "C11") (pin "1") (pinfunction "1_1") (pintype "passive"))
      (node (ref "C14") (pin "1") (pinfunction "1_1") (pintype "passive"))
      (node (ref "C15") (pin "2") (pinfunction "2_2") (pintype "passive"))
      (node (ref "C2") (pin "1") (pinfunction "1_1") (pintype "passive"))
      (node (ref "C22") (pin "1") (pinfunction "1_1") (pintype "passive"))
      (node (ref "C23") (pin "1") (pinfunction "1_1") (pintype "passive"))
      (node (ref "C24") (pin "1") (pinfunction "1_1") (pintype "passive"))
      (node (ref "C3") (pin "1") (pinfunction "1_1") (pintype "passive"))
      (node (ref "C4") (pin "1") (pinfunction "1_1") (pintype "passive"))
      (node (ref "C5") (pin "1") (pinfunction "1_1") (pintype "passive"))
      (node (ref "C6") (pin "2") (pinfunction "2_2") (pintype "passive"))
      (node (ref "C7") (pin "2") (pinfunction "2_2") (pintype "passive"))
      (node (ref "C8") (pin "1") (pinfunction "1_1") (pintype "passive"))
      (node (ref "C9") (pin "1") (pinfunction "1_1") (pintype "passive"))
      (node (ref "DEBUG") (pin "1") (pinfunction "1_1") (pintype "passive"))
      (node (ref "IC1") (pin "11") (pinfunction "HPGND_11") (pintype "passive"))
      (node (ref "IC1") (pin "15") (pinfunction "AGND_15") (pintype "passive"))
      (node (ref "IC1") (pin "28") (pinfunction "DGND_28") (pintype "passive"))
      (node (ref "ICSP1") (pin "6") (pinfunction "6_6") (pintype "passive"))
      (node (ref "J1") (pin "1") (pinfunction "1_1") (pintype "passive"))
      (node (ref "J2") (pin "1") (pinfunction "1_1") (pintype "passive"))
      (node (ref "J3") (pin "1") (pinfunction "1_1") (pintype "passive"))
      (node (ref "J4") (pin "3") (pinfunction "3_3") (pintype "passive"))
      (node (ref "J5") (pin "3") (pinfunction "3_3") (pintype "passive"))
      (node (ref "J6") (pin "3") (pinfunction "3_3") (pintype "passive"))
      (node (ref "J7") (pin "3") (pinfunction "3_3") (pintype "passive"))
      (node (ref "JTAG") (pin "3") (pinfunction "3_3") (pintype "passive"))
      (node (ref "JTAG") (pin "5") (pinfunction "5_5") (pintype "passive"))
      (node (ref "JTAG") (pin "9") (pinfunction "9_9") (pintype "passive"))
      (node (ref "POWER") (pin "6") (pinfunction "6_6") (pintype "passive"))
      (node (ref "POWER") (pin "7") (pinfunction "7_7") (pintype "passive"))
      (node (ref "PWMH") (pin "7") (pinfunction "7_7") (pintype "passive"))
      (node (ref "R1") (pin "2") (pinfunction "2_2") (pintype "passive"))
      (node (ref "R15") (pin "1") (pinfunction "1_1") (pintype "passive"))
      (node (ref "R16") (pin "2") (pinfunction "2_2") (pintype "passive"))
      (node (ref "R19") (pin "1") (pinfunction "1_1") (pintype "passive"))
      (node (ref "R2") (pin "2") (pinfunction "2_2") (pintype "passive"))
      (node (ref "R20") (pin "2") (pinfunction "2_2") (pintype "passive"))
      (node (ref "R21") (pin "1") (pinfunction "1_1") (pintype "passive"))
      (node (ref "R22") (pin "2") (pinfunction "2_2") (pintype "passive"))
      (node (ref "R23") (pin "1") (pinfunction "1_1") (pintype "passive"))
      (node (ref "R24") (pin "1") (pinfunction "1_1") (pintype "passive"))
      (node (ref "R25") (pin "1") (pinfunction "1_1") (pintype "passive"))
      (node (ref "R3") (pin "2") (pinfunction "2_2") (pintype "passive"))
      (node (ref "R4") (pin "2") (pinfunction "2_2") (pintype "passive"))
      (node (ref "SPI") (pin "6") (pinfunction "6_6") (pintype "passive"))
      (node (ref "XIO") (pin "35") (pinfunction "35_35") (pintype "passive"))
      (node (ref "XIO") (pin "36") (pinfunction "36_36") (pintype "passive"))
    )
    (net (code "114") (name "Net-(C1-Pad2)") (class "Default")
      (node (ref "C1") (pin "2") (pinfunction "2_2") (pintype "passive"))
      (node (ref "L1") (pin "1") (pinfunction "1_1") (pintype "passive"))
    )
    (net (code "115") (name "Net-(C12-Pad1)") (class "Default")
      (node (ref "C12") (pin "1") (pinfunction "1_1") (pintype "passive"))
      (node (ref "R13") (pin "2") (pinfunction "2_2") (pintype "passive"))
    )
    (net (code "116") (name "Net-(C12-Pad2)") (class "Default")
      (node (ref "C12") (pin "2") (pinfunction "2_2") (pintype "passive"))
      (node (ref "J1") (pin "5") (pinfunction "5_5") (pintype "passive"))
    )
    (net (code "117") (name "Net-(C13-Pad1)") (class "Default")
      (node (ref "C13") (pin "1") (pinfunction "1_1") (pintype "passive"))
      (node (ref "R14") (pin "2") (pinfunction "2_2") (pintype "passive"))
    )
    (net (code "118") (name "Net-(C13-Pad2)") (class "Default")
      (node (ref "C13") (pin "2") (pinfunction "2_2") (pintype "passive"))
      (node (ref "J1") (pin "2") (pinfunction "2_2") (pintype "passive"))
    )
    (net (code "119") (name "Net-(C14-Pad2)") (class "Default")
      (node (ref "C14") (pin "2") (pinfunction "2_2") (pintype "passive"))
      (node (ref "C16") (pin "2") (pinfunction "2_2") (pintype "passive"))
      (node (ref "R13") (pin "1") (pinfunction "1_1") (pintype "passive"))
      (node (ref "R15") (pin "2") (pinfunction "2_2") (pintype "passive"))
    )
    (net (code "120") (name "Net-(C15-Pad1)") (class "Default")
      (node (ref "C15") (pin "1") (pinfunction "1_1") (pintype "passive"))
      (node (ref "C17") (pin "2") (pinfunction "2_2") (pintype "passive"))
      (node (ref "R14") (pin "1") (pinfunction "1_1") (pintype "passive"))
      (node (ref "R16") (pin "1") (pinfunction "1_1") (pintype "passive"))
    )
    (net (code "121") (name "Net-(C18-Pad2)") (class "Default")
      (node (ref "C18") (pin "2") (pinfunction "2_2") (pintype "passive"))
      (node (ref "R17") (pin "1") (pinfunction "1_1") (pintype "passive"))
      (node (ref "R19") (pin "2") (pinfunction "2_2") (pintype "passive"))
    )
    (net (code "122") (name "Net-(C19-Pad2)") (class "Default")
      (node (ref "C19") (pin "2") (pinfunction "2_2") (pintype "passive"))
      (node (ref "R18") (pin "1") (pinfunction "1_1") (pintype "passive"))
      (node (ref "R20") (pin "1") (pinfunction "1_1") (pintype "passive"))
    )
    (net (code "123") (name "Net-(C20-Pad2)") (class "Default")
      (node (ref "C20") (pin "2") (pinfunction "2_2") (pintype "passive"))
      (node (ref "J3") (pin "5") (pinfunction "5_5") (pintype "passive"))
      (node (ref "R21") (pin "2") (pinfunction "2_2") (pintype "passive"))
    )
    (net (code "124") (name "Net-(C21-Pad2)") (class "Default")
      (node (ref "C21") (pin "2") (pinfunction "2_2") (pintype "passive"))
      (node (ref "J3") (pin "2") (pinfunction "2_2") (pintype "passive"))
      (node (ref "R22") (pin "1") (pinfunction "1_1") (pintype "passive"))
    )
    (net (code "125") (name "Net-(J2-Pad2)") (class "Default")
      (node (ref "J2") (pin "2") (pinfunction "2_2") (pintype "passive"))
      (node (ref "R18") (pin "2") (pinfunction "2_2") (pintype "passive"))
    )
    (net (code "126") (name "Net-(J2-Pad5)") (class "Default")
      (node (ref "J2") (pin "5") (pinfunction "5_5") (pintype "passive"))
      (node (ref "R17") (pin "2") (pinfunction "2_2") (pintype "passive"))
    )
    (net (code "127") (name "Net-(J4-Pad1)") (class "Default")
      (node (ref "J4") (pin "1") (pinfunction "1_1") (pintype "passive"))
      (node (ref "R26") (pin "2") (pinfunction "2_2") (pintype "passive"))
    )
    (net (code "128") (name "Net-(J5-Pad1)") (class "Default")
      (node (ref "J5") (pin "1") (pinfunction "1_1") (pintype "passive"))
      (node (ref "R27") (pin "2") (pinfunction "2_2") (pintype "passive"))
    )
    (net (code "129") (name "Net-(J6-Pad1)") (class "Default")
      (node (ref "J6") (pin "1") (pinfunction "1_1") (pintype "passive"))
      (node (ref "R28") (pin "2") (pinfunction "2_2") (pintype "passive"))
    )
    (net (code "130") (name "Net-(J8-Pad1)") (class "Default")
      (node (ref "J8") (pin "1") (pinfunction "1_1") (pintype "passive"))
      (node (ref "R29") (pin "2") (pinfunction "2_2") (pintype "passive"))
    )
    (net (code "131") (name "Net-(POWER-Pad1)") (class "Default")
      (node (ref "POWER") (pin "1") (pinfunction "1_1") (pintype "passive"))
    )
    (net (code "132") (name "unconnected-(JTAG-Pad7)") (class "Default")
      (node (ref "JTAG") (pin "7") (pinfunction "7_7") (pintype "passive+no_connect"))
    )
  )
)
